# fabwalker-0930-2.net
KiCad netlist of a schematic drawn in EAGLE
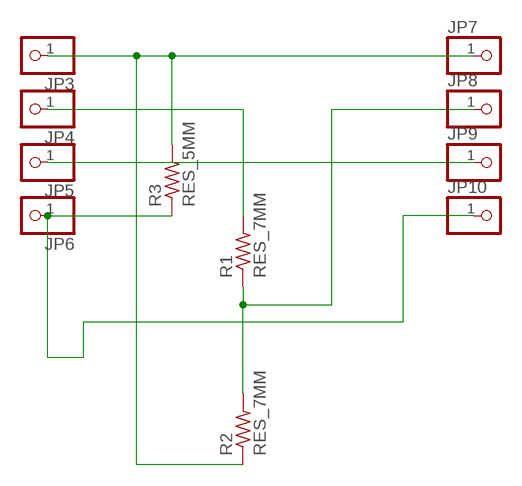
[diagram p0: schematic, sheet 1]

(export (version "E")
  (design (tool "Eeschema 10.0.6"))
  (components
    (comp (ref "JP3")
      (value "PINHD-1X1")
      (footprint "eagle-import:1X01")
      (libsource (lib "eagle-import") (part "PINHD-1X1"))
    )
    (comp (ref "JP4")
      (value "PINHD-1X1")
      (footprint "eagle-import:1X01")
      (libsource (lib "eagle-import") (part "PINHD-1X1"))
    )
    (comp (ref "JP5")
      (value "PINHD-1X1")
      (footprint "eagle-import:1X01")
      (libsource (lib "eagle-import") (part "PINHD-1X1"))
    )
    (comp (ref "JP6")
      (value "PINHD-1X1")
      (footprint "eagle-import:1X01")
      (libsource (lib "eagle-import") (part "PINHD-1X1"))
    )
    (comp (ref "JP7")
      (value "PINHD-1X1")
      (footprint "eagle-import:1X01")
      (libsource (lib "eagle-import") (part "PINHD-1X1"))
    )
    (comp (ref "JP8")
      (value "PINHD-1X1")
      (footprint "eagle-import:1X01")
      (libsource (lib "eagle-import") (part "PINHD-1X1"))
    )
    (comp (ref "JP9")
      (value "PINHD-1X1")
      (footprint "eagle-import:1X01")
      (libsource (lib "eagle-import") (part "PINHD-1X1"))
    )
    (comp (ref "JP10")
      (value "PINHD-1X1")
      (footprint "eagle-import:1X01")
      (libsource (lib "eagle-import") (part "PINHD-1X1"))
    )
    (comp (ref "R1")
      (value "RES_7MM")
      (footprint "eagle-import:0204_7")
      (libsource (lib "eagle-import") (part "RES_7MM"))
    )
    (comp (ref "R2")
      (value "RES_7MM")
      (footprint "eagle-import:0204_7")
      (libsource (lib "eagle-import") (part "RES_7MM"))
    )
    (comp (ref "R3")
      (value "RES_5MM")
      (footprint "eagle-import:0204_5")
      (libsource (lib "eagle-import") (part "RES_5MM"))
    )
  )
  (nets
    (net (code "1") (name "Net-(JP3-Pad1)") (class "Default")
      (node (ref "JP3") (pin "1") (pinfunction "1_1") (pintype "passive"))
      (node (ref "JP7") (pin "1") (pinfunction "1_1") (pintype "passive"))
      (node (ref "R2") (pin "1") (pinfunction "1_1") (pintype "passive"))
      (node (ref "R3") (pin "2") (pinfunction "2_2") (pintype "passive"))
    )
    (net (code "2") (name "Net-(JP4-Pad1)") (class "Default")
      (node (ref "JP4") (pin "1") (pinfunction "1_1") (pintype "passive"))
      (node (ref "R1") (pin "2") (pinfunction "2_2") (pintype "passive"))
    )
    (net (code "3") (name "Net-(JP5-Pad1)") (class "Default")
      (node (ref "JP5") (pin "1") (pinfunction "1_1") (pintype "passive"))
      (node (ref "JP9") (pin "1") (pinfunction "1_1") (pintype "passive"))
    )
    (net (code "4") (name "Net-(JP8-Pad1)") (class "Default")
      (node (ref "JP8") (pin "1") (pinfunction "1_1") (pintype "passive"))
      (node (ref "R1") (pin "1") (pinfunction "1_1") (pintype "passive"))
      (node (ref "R2") (pin "2") (pinfunction "2_2") (pintype "passive"))
    )
    (net (code "5") (name "Net-(JP10-Pad1)") (class "Default")
      (node (ref "JP10") (pin "1") (pinfunction "1_1") (pintype "passive"))
      (node (ref "JP6") (pin "1") (pinfunction "1_1") (pintype "passive"))
      (node (ref "R3") (pin "1") (pinfunction "1_1") (pintype "passive"))
    )
  )
)
